# Lagopus_B_2.net
KiCad netlist of a schematic drawn in EAGLE
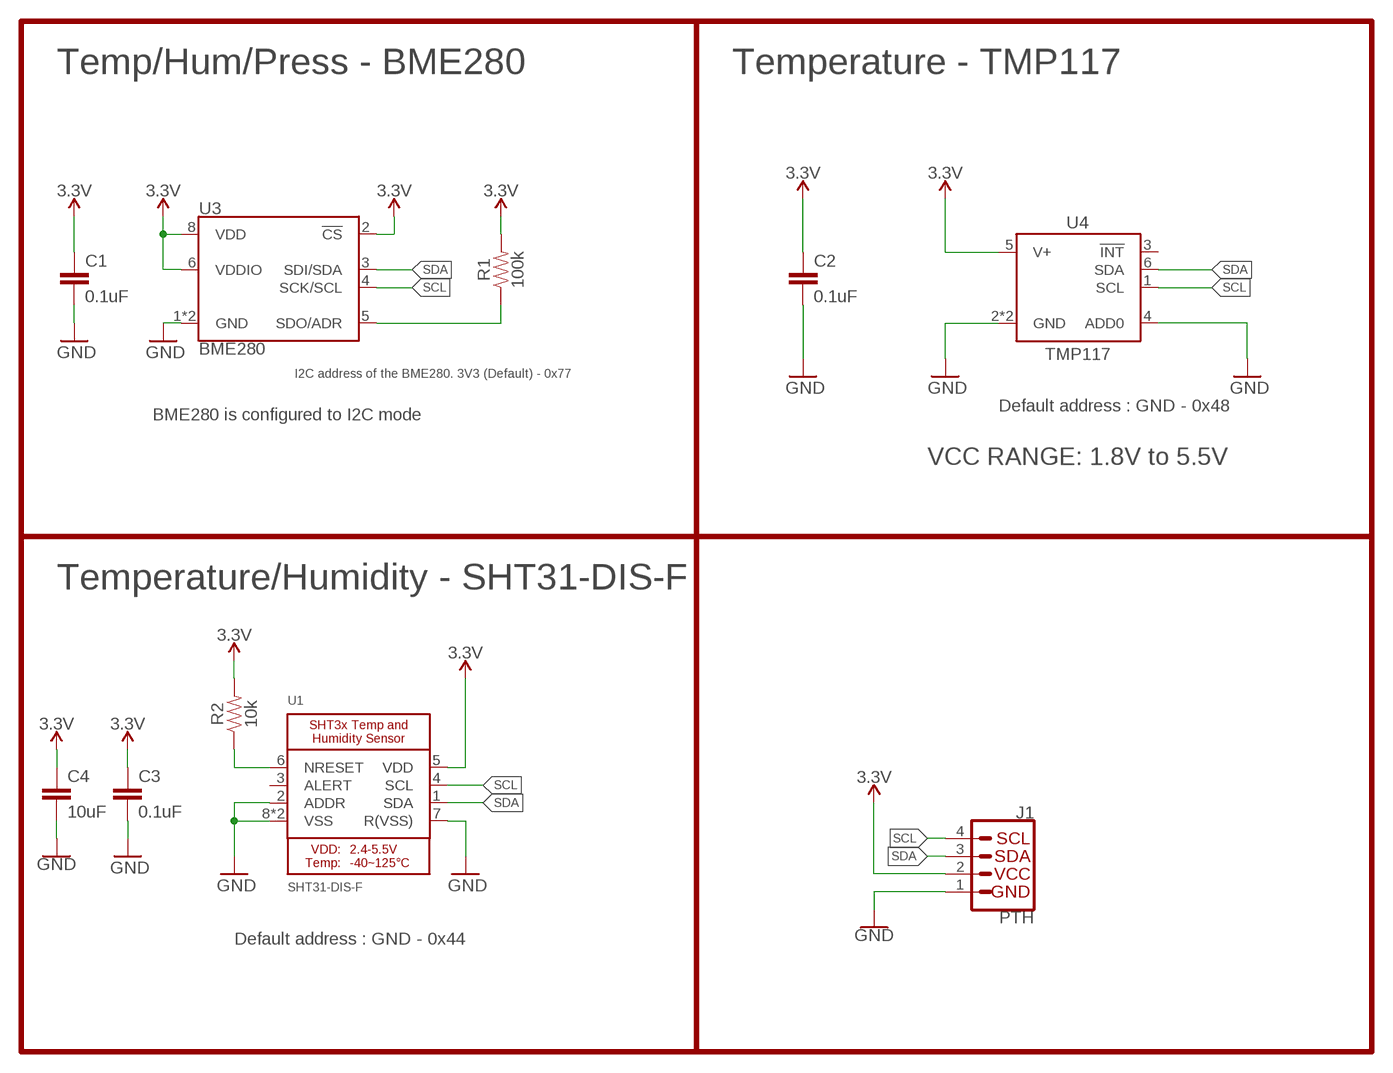
[diagram p0: schematic, sheet 1]

(export (version "E")
  (design (tool "Eeschema 10.0.6"))
  (components
    (comp (ref "C1")
      (value "0.1uF")
      (footprint "eagle-import:0603")
      (libsource (lib "eagle-import") (part "0.1UF-0603-25V-(+80/-20%)"))
    )
    (comp (ref "C2")
      (value "0.1uF")
      (footprint "eagle-import:0603")
      (libsource (lib "eagle-import") (part "0.1UF-0603-25V-(+80/-20%)"))
    )
    (comp (ref "C3")
      (value "0.1uF")
      (footprint "eagle-import:0603")
      (libsource (lib "eagle-import") (part "0.1UF-0603-25V-(+80/-20%)"))
    )
    (comp (ref "C4")
      (value "10uF")
      (footprint "eagle-import:0603")
      (libsource (lib "eagle-import") (part "10UF-0603-6.3V-20%"))
    )
    (comp (ref "J1")
      (value "PTH")
      (footprint "eagle-import:1X04_NO_SILK")
      (libsource (lib "eagle-import") (part "I2C_STANDARD_NO_SILK"))
    )
    (comp (ref "R1")
      (value "100k")
      (footprint "eagle-import:0603")
      (libsource (lib "eagle-import") (part "100KOHM-0603-1/10W-1%"))
    )
    (comp (ref "R2")
      (value "10k")
      (footprint "eagle-import:0603")
      (libsource (lib "eagle-import") (part "10KOHM-0603-1/10W-1%"))
    )
    (comp (ref "U1")
      (value "SHT31-DIS-F")
      (footprint "eagle-import:SHT3X")
      (libsource (lib "eagle-import") (part "SHT3X"))
    )
    (comp (ref "U3")
      (value "BME280")
      (footprint "eagle-import:LGA-8-2.5X2.5")
      (libsource (lib "eagle-import") (part "BME280"))
    )
    (comp (ref "U4")
      (value "TMP117")
      (footprint "eagle-import:TMP117")
      (libsource (lib "eagle-import") (part "TMP117"))
    )
  )
  (nets
    (net (code "1") (name "3.3V") (class "Default")
      (node (ref "C1") (pin "1") (pinfunction "1_1") (pintype "passive"))
      (node (ref "C2") (pin "1") (pinfunction "1_1") (pintype "passive"))
      (node (ref "C3") (pin "1") (pinfunction "1_1") (pintype "passive"))
      (node (ref "C4") (pin "1") (pinfunction "1_1") (pintype "passive"))
      (node (ref "J1") (pin "2") (pinfunction "VCC_2") (pintype "power_in"))
      (node (ref "R1") (pin "2") (pinfunction "2_2") (pintype "passive"))
      (node (ref "R2") (pin "2") (pinfunction "2_2") (pintype "passive"))
      (node (ref "U1") (pin "5") (pinfunction "VDD_5") (pintype "power_in"))
      (node (ref "U3") (pin "2") (pinfunction "~{CS}_2") (pintype "bidirectional"))
      (node (ref "U3") (pin "6") (pinfunction "VDDIO_6") (pintype "bidirectional"))
      (node (ref "U3") (pin "8") (pinfunction "VDD_8") (pintype "bidirectional"))
      (node (ref "U4") (pin "5") (pinfunction "V+_5") (pintype "power_in"))
    )
    (net (code "2") (name "GND") (class "Default")
      (node (ref "C1") (pin "2") (pinfunction "2_2") (pintype "passive"))
      (node (ref "C2") (pin "2") (pinfunction "2_2") (pintype "passive"))
      (node (ref "C3") (pin "2") (pinfunction "2_2") (pintype "passive"))
      (node (ref "C4") (pin "2") (pinfunction "2_2") (pintype "passive"))
      (node (ref "J1") (pin "1") (pinfunction "GND_1") (pintype "power_in"))
      (node (ref "U1") (pin "2") (pinfunction "ADDR_2") (pintype "bidirectional"))
      (node (ref "U1") (pin "7") (pinfunction "R(VSS)_7") (pintype "bidirectional"))
      (node (ref "U1") (pin "8") (pinfunction "VSS_8") (pintype "power_in"))
      (node (ref "U1") (pin "THERMAL") (pinfunction "VSS_THERMAL") (pintype "power_in"))
      (node (ref "U3") (pin "1") (pinfunction "GND_1") (pintype "bidirectional"))
      (node (ref "U3") (pin "7") (pinfunction "GND_7") (pintype "bidirectional"))
      (node (ref "U4") (pin "2") (pinfunction "GND_2") (pintype "bidirectional"))
      (node (ref "U4") (pin "4") (pinfunction "ADD0_4") (pintype "bidirectional"))
      (node (ref "U4") (pin "THERMAL") (pinfunction "GND_THERMAL") (pintype "bidirectional"))
    )
    (net (code "3") (name "Net-(U1-NRESET)") (class "Default")
      (node (ref "R2") (pin "1") (pinfunction "1_1") (pintype "passive"))
      (node (ref "U1") (pin "6") (pinfunction "NRESET_6") (pintype "bidirectional"))
    )
    (net (code "4") (name "Net-(U3-SDO{slash}ADR)") (class "Default")
      (node (ref "R1") (pin "1") (pinfunction "1_1") (pintype "passive"))
      (node (ref "U3") (pin "5") (pinfunction "SDO/ADR_5") (pintype "bidirectional"))
    )
    (net (code "5") (name "SCL") (class "Default")
      (node (ref "J1") (pin "4") (pinfunction "SCL_4") (pintype "passive"))
      (node (ref "U1") (pin "4") (pinfunction "SCL_4") (pintype "bidirectional"))
      (node (ref "U3") (pin "4") (pinfunction "SCK/SCL_4") (pintype "bidirectional"))
      (node (ref "U4") (pin "1") (pinfunction "SCL_1") (pintype "bidirectional"))
    )
    (net (code "6") (name "SDA") (class "Default")
      (node (ref "J1") (pin "3") (pinfunction "SDA_3") (pintype "passive"))
      (node (ref "U1") (pin "1") (pinfunction "SDA_1") (pintype "bidirectional"))
      (node (ref "U3") (pin "3") (pinfunction "SDI/SDA_3") (pintype "bidirectional"))
      (node (ref "U4") (pin "6") (pinfunction "SDA_6") (pintype "bidirectional"))
    )
    (net (code "7") (name "unconnected-(U1-ALERT-Pad3)") (class "Default")
      (node (ref "U1") (pin "3") (pinfunction "ALERT_3") (pintype "bidirectional"))
    )
    (net (code "8") (name "unconnected-(U4-~{INT}-Pad3)") (class "Default")
      (node (ref "U4") (pin "3") (pinfunction "~{INT}_3") (pintype "bidirectional"))
    )
  )
)
